# SENSORS.net
KiCad netlist of a schematic drawn in Altium Designer
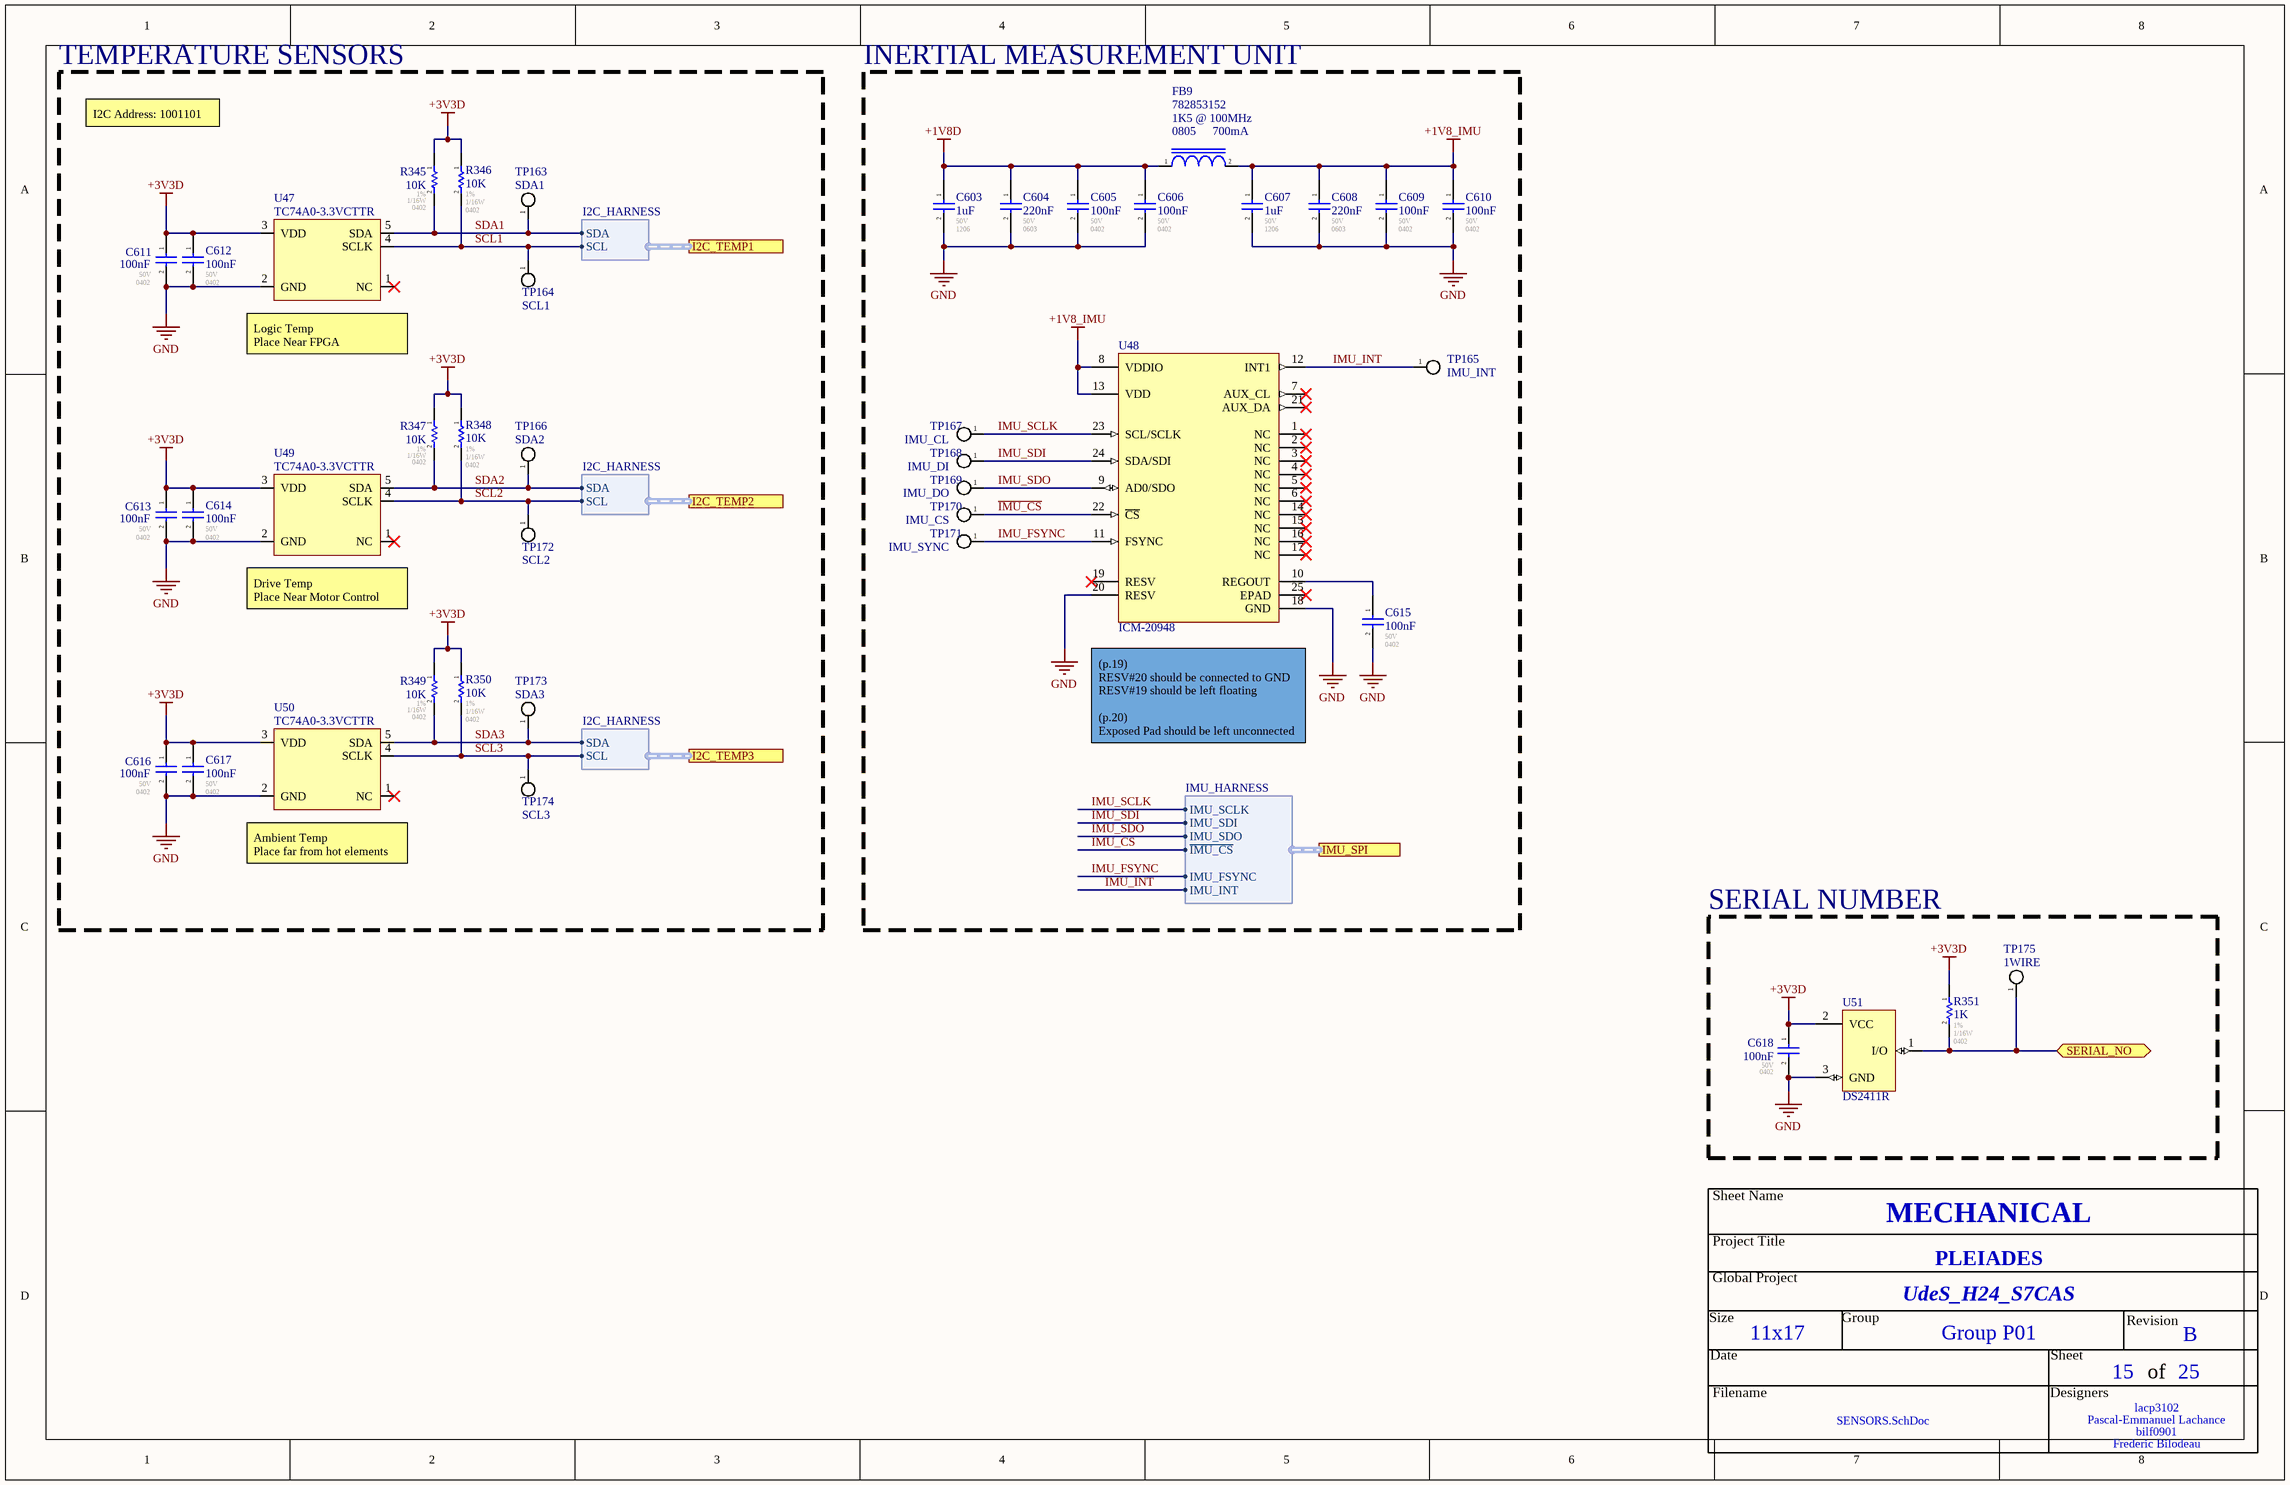
[diagram p0: SENSORS.SchDoc]

(export (version "E")
  (design (tool "Eeschema 10.0.6"))
  (components
    (comp (ref "C603")
      (value "1uF")
      (footprint "1206")
      (description "GCJ31CR71H105KA12L\r\n1206 1uF 10% X7R Ceramic Capacitor")
      (fields
        (field (name "MFR") "Murata")
        (field (name "PART#") "GCJ31CR71H105KA12L")
        (field (name "VOLTAGE - RATED") "50V")
      )
      (libsource (lib "Symbols") (part "CAP_CER"))
    )
    (comp (ref "C604")
      (value "220nF")
      (footprint "0603")
      (description "GCM188R71H224KA64D\r\n0603 220nF 10% X7R Ceramic Capacitor")
      (fields
        (field (name "MFR") "Murata")
        (field (name "PART#") "GCM188R71H224KA64D")
        (field (name "VOLTAGE - RATED") "50V")
      )
      (libsource (lib "Symbols") (part "CAP_CER"))
    )
    (comp (ref "C605")
      (value "100nF")
      (footprint "0402")
      (description "GCM155R71H104KE02J\r\n0402 100nF 10% X7R Ceramic Capacitor")
      (fields
        (field (name "MFR") "Murata")
        (field (name "PART#") "GCM155R71H104KE02J")
        (field (name "VOLTAGE - RATED") "50V")
      )
      (libsource (lib "Symbols") (part "CAP_CER"))
    )
    (comp (ref "C606")
      (value "100nF")
      (footprint "0402")
      (description "GCM155R71H104KE02J\r\n0402 100nF 10% X7R Ceramic Capacitor")
      (fields
        (field (name "MFR") "Murata")
        (field (name "PART#") "GCM155R71H104KE02J")
        (field (name "VOLTAGE - RATED") "50V")
      )
      (libsource (lib "Symbols") (part "CAP_CER"))
    )
    (comp (ref "C607")
      (value "1uF")
      (footprint "1206")
      (description "GCJ31CR71H105KA12L\r\n1206 1uF 10% X7R Ceramic Capacitor")
      (fields
        (field (name "MFR") "Murata")
        (field (name "PART#") "GCJ31CR71H105KA12L")
        (field (name "VOLTAGE - RATED") "50V")
      )
      (libsource (lib "Symbols") (part "CAP_CER"))
    )
    (comp (ref "C608")
      (value "220nF")
      (footprint "0603")
      (description "GCM188R71H224KA64D\r\n0603 220nF 10% X7R Ceramic Capacitor")
      (fields
        (field (name "MFR") "Murata")
        (field (name "PART#") "GCM188R71H224KA64D")
        (field (name "VOLTAGE - RATED") "50V")
      )
      (libsource (lib "Symbols") (part "CAP_CER"))
    )
    (comp (ref "C609")
      (value "100nF")
      (footprint "0402")
      (description "GCM155R71H104KE02J\r\n0402 100nF 10% X7R Ceramic Capacitor")
      (fields
        (field (name "MFR") "Murata")
        (field (name "PART#") "GCM155R71H104KE02J")
        (field (name "VOLTAGE - RATED") "50V")
      )
      (libsource (lib "Symbols") (part "CAP_CER"))
    )
    (comp (ref "C610")
      (value "100nF")
      (footprint "0402")
      (description "GCM155R71H104KE02J\r\n0402 100nF 10% X7R Ceramic Capacitor")
      (fields
        (field (name "MFR") "Murata")
        (field (name "PART#") "GCM155R71H104KE02J")
        (field (name "VOLTAGE - RATED") "50V")
      )
      (libsource (lib "Symbols") (part "CAP_CER"))
    )
    (comp (ref "C611")
      (value "100nF")
      (footprint "0402")
      (description "GCM155R71H104KE02J\r\n0402 100nF 10% X7R Ceramic Capacitor")
      (fields
        (field (name "MFR") "Murata")
        (field (name "PART#") "GCM155R71H104KE02J")
        (field (name "VOLTAGE - RATED") "50V")
      )
      (libsource (lib "Symbols") (part "CAP_CER"))
    )
    (comp (ref "C612")
      (value "100nF")
      (footprint "0402")
      (description "GCM155R71H104KE02J\r\n0402 100nF 10% X7R Ceramic Capacitor")
      (fields
        (field (name "MFR") "Murata")
        (field (name "PART#") "GCM155R71H104KE02J")
        (field (name "VOLTAGE - RATED") "50V")
      )
      (libsource (lib "Symbols") (part "CAP_CER"))
    )
    (comp (ref "C613")
      (value "100nF")
      (footprint "0402")
      (description "GCM155R71H104KE02J\r\n0402 100nF 10% X7R Ceramic Capacitor")
      (fields
        (field (name "MFR") "Murata")
        (field (name "PART#") "GCM155R71H104KE02J")
        (field (name "VOLTAGE - RATED") "50V")
      )
      (libsource (lib "Symbols") (part "CAP_CER"))
    )
    (comp (ref "C614")
      (value "100nF")
      (footprint "0402")
      (description "GCM155R71H104KE02J\r\n0402 100nF 10% X7R Ceramic Capacitor")
      (fields
        (field (name "MFR") "Murata")
        (field (name "PART#") "GCM155R71H104KE02J")
        (field (name "VOLTAGE - RATED") "50V")
      )
      (libsource (lib "Symbols") (part "CAP_CER"))
    )
    (comp (ref "C615")
      (value "100nF")
      (footprint "0402")
      (description "GCM155R71H104KE02J\r\n0402 100nF 10% X7R Ceramic Capacitor")
      (fields
        (field (name "MFR") "Murata")
        (field (name "PART#") "GCM155R71H104KE02J")
        (field (name "VOLTAGE - RATED") "50V")
      )
      (libsource (lib "Symbols") (part "CAP_CER"))
    )
    (comp (ref "C616")
      (value "100nF")
      (footprint "0402")
      (description "GCM155R71H104KE02J\r\n0402 100nF 10% X7R Ceramic Capacitor")
      (fields
        (field (name "MFR") "Murata")
        (field (name "PART#") "GCM155R71H104KE02J")
        (field (name "VOLTAGE - RATED") "50V")
      )
      (libsource (lib "Symbols") (part "CAP_CER"))
    )
    (comp (ref "C617")
      (value "100nF")
      (footprint "0402")
      (description "GCM155R71H104KE02J\r\n0402 100nF 10% X7R Ceramic Capacitor")
      (fields
        (field (name "MFR") "Murata")
        (field (name "PART#") "GCM155R71H104KE02J")
        (field (name "VOLTAGE - RATED") "50V")
      )
      (libsource (lib "Symbols") (part "CAP_CER"))
    )
    (comp (ref "C618")
      (value "100nF")
      (footprint "0402")
      (description "GCM155R71H104KE02J\r\n0402 100nF 10% X7R Ceramic Capacitor")
      (fields
        (field (name "MFR") "Murata")
        (field (name "PART#") "GCM155R71H104KE02J")
        (field (name "VOLTAGE - RATED") "50V")
      )
      (libsource (lib "Symbols") (part "CAP_CER"))
    )
    (comp (ref "FB9")
      (value "782853152")
      (footprint "IND_0805")
      (description "600 Ohms @ 100 MHz 1 Signal Line Ferrite Bead 0603 (1608 Metric) 1A 200mOhm")
      (fields
        (field (name "IMPEDANCE @ FREQ") "1K5 @ 100MHz")
        (field (name "PACKAGE / CASE") "0805")
        (field (name "CURRENT RATING") "700mA")
        (field (name "MANUFACTURER") "Wurth Elektronik")
      )
      (libsource (lib "Symbols") (part "FERRITE_BEAD"))
    )
    (comp (ref "R345")
      (value "10K")
      (footprint "RES_0402")
      (fields
        (field (name "TOLERANCE") "1%")
        (field (name "POWER") "1/16W")
        (field (name "PACKAGE / CASE") "0402")
      )
      (libsource (lib "Symbols") (part "RESISTOR"))
    )
    (comp (ref "R346")
      (value "10K")
      (footprint "RES_0402")
      (fields
        (field (name "TOLERANCE") "1%")
        (field (name "POWER") "1/16W")
        (field (name "PACKAGE / CASE") "0402")
      )
      (libsource (lib "Symbols") (part "RESISTOR"))
    )
    (comp (ref "R347")
      (value "10K")
      (footprint "RES_0402")
      (fields
        (field (name "TOLERANCE") "1%")
        (field (name "POWER") "1/16W")
        (field (name "PACKAGE / CASE") "0402")
      )
      (libsource (lib "Symbols") (part "RESISTOR"))
    )
    (comp (ref "R348")
      (value "10K")
      (footprint "RES_0402")
      (fields
        (field (name "TOLERANCE") "1%")
        (field (name "POWER") "1/16W")
        (field (name "PACKAGE / CASE") "0402")
      )
      (libsource (lib "Symbols") (part "RESISTOR"))
    )
    (comp (ref "R349")
      (value "10K")
      (footprint "RES_0402")
      (fields
        (field (name "TOLERANCE") "1%")
        (field (name "POWER") "1/16W")
        (field (name "PACKAGE / CASE") "0402")
      )
      (libsource (lib "Symbols") (part "RESISTOR"))
    )
    (comp (ref "R350")
      (value "10K")
      (footprint "RES_0402")
      (fields
        (field (name "TOLERANCE") "1%")
        (field (name "POWER") "1/16W")
        (field (name "PACKAGE / CASE") "0402")
      )
      (libsource (lib "Symbols") (part "RESISTOR"))
    )
    (comp (ref "R351")
      (value "1K")
      (footprint "RES_0402")
      (fields
        (field (name "TOLERANCE") "1%")
        (field (name "POWER") "1/16W")
        (field (name "PACKAGE / CASE") "0402")
      )
      (libsource (lib "Symbols") (part "RESISTOR"))
    )
    (comp (ref "TP163")
      (value "SDA1")
      (footprint "TP_PAD_SMALL")
      (description "Test Point")
      (libsource (lib "Symbols") (part "TESTPOINT_PAD_SMALL"))
    )
    (comp (ref "TP164")
      (value "SCL1")
      (footprint "TP_PAD_SMALL")
      (description "Test Point")
      (libsource (lib "Symbols") (part "TESTPOINT_PAD_SMALL"))
    )
    (comp (ref "TP165")
      (value "IMU_INT")
      (footprint "TP_PAD_SMALL")
      (description "Test Point")
      (libsource (lib "Symbols") (part "TESTPOINT_PAD_SMALL"))
    )
    (comp (ref "TP166")
      (value "SDA2")
      (footprint "TP_PAD_SMALL")
      (description "Test Point")
      (libsource (lib "Symbols") (part "TESTPOINT_PAD_SMALL"))
    )
    (comp (ref "TP167")
      (value "IMU_CL")
      (footprint "TP_PAD_SMALL")
      (description "Test Point")
      (libsource (lib "Symbols") (part "TESTPOINT_PAD_SMALL"))
    )
    (comp (ref "TP168")
      (value "IMU_DI")
      (footprint "TP_PAD_SMALL")
      (description "Test Point")
      (libsource (lib "Symbols") (part "TESTPOINT_PAD_SMALL"))
    )
    (comp (ref "TP169")
      (value "IMU_DO")
      (footprint "TP_PAD_SMALL")
      (description "Test Point")
      (libsource (lib "Symbols") (part "TESTPOINT_PAD_SMALL"))
    )
    (comp (ref "TP170")
      (value "IMU_CS")
      (footprint "TP_PAD_SMALL")
      (description "Test Point")
      (libsource (lib "Symbols") (part "TESTPOINT_PAD_SMALL"))
    )
    (comp (ref "TP171")
      (value "IMU_SYNC")
      (footprint "TP_PAD_SMALL")
      (description "Test Point")
      (libsource (lib "Symbols") (part "TESTPOINT_PAD_SMALL"))
    )
    (comp (ref "TP172")
      (value "SCL2")
      (footprint "TP_PAD_SMALL")
      (description "Test Point")
      (libsource (lib "Symbols") (part "TESTPOINT_PAD_SMALL"))
    )
    (comp (ref "TP173")
      (value "SDA3")
      (footprint "TP_PAD_SMALL")
      (description "Test Point")
      (libsource (lib "Symbols") (part "TESTPOINT_PAD_SMALL"))
    )
    (comp (ref "TP174")
      (value "SCL3")
      (footprint "TP_PAD_SMALL")
      (description "Test Point")
      (libsource (lib "Symbols") (part "TESTPOINT_PAD_SMALL"))
    )
    (comp (ref "TP175")
      (value "1WIRE")
      (footprint "TP_PAD_SMALL")
      (description "Test Point")
      (libsource (lib "Symbols") (part "TESTPOINT_PAD_SMALL"))
    )
    (comp (ref "U47")
      (value "TC74A0-3.3VCTTR")
      (footprint "SEN_TEMP_TC74A0-3.3VCTTR")
      (description "SENS - TEMPERATURE SENSOR I2C/SMBUS - SOT23-5")
      (fields
        (field (name "VOLTAGE") "2.7 V ~ 5.5 V")
        (field (name "MFG") "Microchip")
        (field (name "CREATEDBY") "Jonathan Bouchard")
      )
      (libsource (lib "S7CAS_LIB2023") (part "SENS_TEMP_TC74A0-3.3VCTTR"))
    )
    (comp (ref "U48")
      (value "ICM-20948")
      (footprint "QFN-24_3X3")
      (description "Accelerometer, Gyroscope, Magnetometer, 9 Axis Sensor I2C, SPI Output")
      (fields (field (name "MFR") "TDK InvenSense"))
      (libsource (lib "Misc") (part "ICM-20948"))
    )
    (comp (ref "U49")
      (value "TC74A0-3.3VCTTR")
      (footprint "SEN_TEMP_TC74A0-3.3VCTTR")
      (description "SENS - TEMPERATURE SENSOR I2C/SMBUS - SOT23-5")
      (fields
        (field (name "VOLTAGE") "2.7 V ~ 5.5 V")
        (field (name "MFG") "Microchip")
        (field (name "CREATEDBY") "Jonathan Bouchard")
      )
      (libsource (lib "S7CAS_LIB2023") (part "SENS_TEMP_TC74A0-3.3VCTTR"))
    )
    (comp (ref "U50")
      (value "TC74A0-3.3VCTTR")
      (footprint "SEN_TEMP_TC74A0-3.3VCTTR")
      (description "SENS - TEMPERATURE SENSOR I2C/SMBUS - SOT23-5")
      (fields
        (field (name "VOLTAGE") "2.7 V ~ 5.5 V")
        (field (name "MFG") "Microchip")
        (field (name "CREATEDBY") "Jonathan Bouchard")
      )
      (libsource (lib "S7CAS_LIB2023") (part "SENS_TEMP_TC74A0-3.3VCTTR"))
    )
    (comp (ref "U51")
      (value "DS2411R")
      (footprint "SOT23-3")
      (description "Silicon Serial Number SOT-23-3")
      (fields (field (name "MFR") "Analog Devices"))
      (libsource (lib "Misc") (part "DS2411R"))
    )
  )
  (nets
    (net (code "3") (name "+1V8D") (class "Default")
      (node (ref "C603") (pin "1") (pinfunction "1_1") (pintype "passive"))
      (node (ref "C604") (pin "1") (pinfunction "1_1") (pintype "passive"))
      (node (ref "C605") (pin "1") (pinfunction "1_1") (pintype "passive"))
      (node (ref "C606") (pin "1") (pinfunction "1_1") (pintype "passive"))
      (node (ref "FB9") (pin "1") (pinfunction "1_1") (pintype "passive"))
    )
    (net (code "4") (name "+1V8_IMU") (class "Default")
      (node (ref "C607") (pin "1") (pinfunction "1_1") (pintype "passive"))
      (node (ref "C608") (pin "1") (pinfunction "1_1") (pintype "passive"))
      (node (ref "C609") (pin "1") (pinfunction "1_1") (pintype "passive"))
      (node (ref "C610") (pin "1") (pinfunction "1_1") (pintype "passive"))
      (node (ref "FB9") (pin "2") (pinfunction "2_2") (pintype "passive"))
      (node (ref "U48") (pin "13") (pinfunction "VDD_13") (pintype "power_in"))
      (node (ref "U48") (pin "8") (pinfunction "VDDIO_8") (pintype "power_in"))
    )
    (net (code "5") (name "+3V3D") (class "Default")
      (node (ref "C611") (pin "1") (pinfunction "1_1") (pintype "passive"))
      (node (ref "C612") (pin "1") (pinfunction "1_1") (pintype "passive"))
      (node (ref "C613") (pin "1") (pinfunction "1_1") (pintype "passive"))
      (node (ref "C614") (pin "1") (pinfunction "1_1") (pintype "passive"))
      (node (ref "C616") (pin "1") (pinfunction "1_1") (pintype "passive"))
      (node (ref "C617") (pin "1") (pinfunction "1_1") (pintype "passive"))
      (node (ref "C618") (pin "1") (pinfunction "1_1") (pintype "passive"))
      (node (ref "R345") (pin "1") (pinfunction "1_1") (pintype "passive"))
      (node (ref "R346") (pin "1") (pinfunction "1_1") (pintype "passive"))
      (node (ref "R347") (pin "1") (pinfunction "1_1") (pintype "passive"))
      (node (ref "R348") (pin "1") (pinfunction "1_1") (pintype "passive"))
      (node (ref "R349") (pin "1") (pinfunction "1_1") (pintype "passive"))
      (node (ref "R350") (pin "1") (pinfunction "1_1") (pintype "passive"))
      (node (ref "R351") (pin "1") (pinfunction "1_1") (pintype "passive"))
      (node (ref "U47") (pin "3") (pinfunction "VDD_3") (pintype "passive"))
      (node (ref "U49") (pin "3") (pinfunction "VDD_3") (pintype "passive"))
      (node (ref "U50") (pin "3") (pinfunction "VDD_3") (pintype "passive"))
      (node (ref "U51") (pin "2") (pinfunction "VCC_2") (pintype "power_in"))
    )
    (net (code "6") (name "/IMU_CS") (class "Default")
      (node (ref "TP170") (pin "1") (pinfunction "A_1") (pintype "passive"))
      (node (ref "U48") (pin "22") (pinfunction "CS_22") (pintype "input"))
    )
    (net (code "7") (name "/IMU_FSYNC") (class "Default")
      (node (ref "TP171") (pin "1") (pinfunction "A_1") (pintype "passive"))
      (node (ref "U48") (pin "11") (pinfunction "FSYNC_11") (pintype "input"))
    )
    (net (code "8") (name "/IMU_INT") (class "Default")
      (node (ref "TP165") (pin "1") (pinfunction "A_1") (pintype "passive"))
      (node (ref "U48") (pin "12") (pinfunction "INT1_12") (pintype "output"))
    )
    (net (code "9") (name "/IMU_SCLK") (class "Default")
      (node (ref "TP167") (pin "1") (pinfunction "A_1") (pintype "passive"))
      (node (ref "U48") (pin "23") (pinfunction "SCL/SCLK_23") (pintype "input"))
    )
    (net (code "10") (name "/IMU_SDI") (class "Default")
      (node (ref "TP168") (pin "1") (pinfunction "A_1") (pintype "passive"))
      (node (ref "U48") (pin "24") (pinfunction "SDA/SDI_24") (pintype "input"))
    )
    (net (code "11") (name "/IMU_SDO") (class "Default")
      (node (ref "TP169") (pin "1") (pinfunction "A_1") (pintype "passive"))
      (node (ref "U48") (pin "9") (pinfunction "AD0/SDO_9") (pintype "bidirectional"))
    )
    (net (code "12") (name "/SCL1") (class "Default")
      (node (ref "R346") (pin "2") (pinfunction "2_2") (pintype "passive"))
      (node (ref "TP164") (pin "1") (pinfunction "A_1") (pintype "passive"))
      (node (ref "U47") (pin "4") (pinfunction "SCLK_4") (pintype "passive"))
    )
    (net (code "13") (name "/SCL2") (class "Default")
      (node (ref "R348") (pin "2") (pinfunction "2_2") (pintype "passive"))
      (node (ref "TP172") (pin "1") (pinfunction "A_1") (pintype "passive"))
      (node (ref "U49") (pin "4") (pinfunction "SCLK_4") (pintype "passive"))
    )
    (net (code "14") (name "/SCL3") (class "Default")
      (node (ref "R350") (pin "2") (pinfunction "2_2") (pintype "passive"))
      (node (ref "TP174") (pin "1") (pinfunction "A_1") (pintype "passive"))
      (node (ref "U50") (pin "4") (pinfunction "SCLK_4") (pintype "passive"))
    )
    (net (code "15") (name "/SDA1") (class "Default")
      (node (ref "R345") (pin "2") (pinfunction "2_2") (pintype "passive"))
      (node (ref "TP163") (pin "1") (pinfunction "A_1") (pintype "passive"))
      (node (ref "U47") (pin "5") (pinfunction "SDA_5") (pintype "passive"))
    )
    (net (code "16") (name "/SDA2") (class "Default")
      (node (ref "R347") (pin "2") (pinfunction "2_2") (pintype "passive"))
      (node (ref "TP166") (pin "1") (pinfunction "A_1") (pintype "passive"))
      (node (ref "U49") (pin "5") (pinfunction "SDA_5") (pintype "passive"))
    )
    (net (code "17") (name "/SDA3") (class "Default")
      (node (ref "R349") (pin "2") (pinfunction "2_2") (pintype "passive"))
      (node (ref "TP173") (pin "1") (pinfunction "A_1") (pintype "passive"))
      (node (ref "U50") (pin "5") (pinfunction "SDA_5") (pintype "passive"))
    )
    (net (code "18") (name "/SERIAL_NO") (class "Default")
      (node (ref "R351") (pin "2") (pinfunction "2_2") (pintype "passive"))
      (node (ref "TP175") (pin "1") (pinfunction "A_1") (pintype "passive"))
      (node (ref "U51") (pin "1") (pinfunction "I/O_1") (pintype "bidirectional"))
    )
    (net (code "21") (name "GND") (class "Default")
      (node (ref "C603") (pin "2") (pinfunction "2_2") (pintype "passive"))
      (node (ref "C604") (pin "2") (pinfunction "2_2") (pintype "passive"))
      (node (ref "C605") (pin "2") (pinfunction "2_2") (pintype "passive"))
      (node (ref "C606") (pin "2") (pinfunction "2_2") (pintype "passive"))
      (node (ref "C607") (pin "2") (pinfunction "2_2") (pintype "passive"))
      (node (ref "C608") (pin "2") (pinfunction "2_2") (pintype "passive"))
      (node (ref "C609") (pin "2") (pinfunction "2_2") (pintype "passive"))
      (node (ref "C610") (pin "2") (pinfunction "2_2") (pintype "passive"))
      (node (ref "C611") (pin "2") (pinfunction "2_2") (pintype "passive"))
      (node (ref "C612") (pin "2") (pinfunction "2_2") (pintype "passive"))
      (node (ref "C613") (pin "2") (pinfunction "2_2") (pintype "passive"))
      (node (ref "C614") (pin "2") (pinfunction "2_2") (pintype "passive"))
      (node (ref "C615") (pin "2") (pinfunction "2_2") (pintype "passive"))
      (node (ref "C616") (pin "2") (pinfunction "2_2") (pintype "passive"))
      (node (ref "C617") (pin "2") (pinfunction "2_2") (pintype "passive"))
      (node (ref "C618") (pin "2") (pinfunction "2_2") (pintype "passive"))
      (node (ref "U47") (pin "2") (pinfunction "GND_2") (pintype "passive"))
      (node (ref "U48") (pin "18") (pinfunction "GND_18") (pintype "power_in"))
      (node (ref "U48") (pin "20") (pinfunction "RESV_20") (pintype "passive"))
      (node (ref "U49") (pin "2") (pinfunction "GND_2") (pintype "passive"))
      (node (ref "U50") (pin "2") (pinfunction "GND_2") (pintype "passive"))
      (node (ref "U51") (pin "3") (pinfunction "GND_3") (pintype "bidirectional"))
    )
    (net (code "22") (name "Net-(U48-REGOUT)") (class "Default")
      (node (ref "C615") (pin "1") (pinfunction "1_1") (pintype "passive"))
      (node (ref "U48") (pin "10") (pinfunction "REGOUT_10") (pintype "power_in"))
    )
    (net (code "23") (name "unconnected-(U47-NC-Pad1)") (class "Default")
      (node (ref "U47") (pin "1") (pinfunction "NC_1") (pintype "passive+no_connect"))
    )
    (net (code "24") (name "unconnected-(U48-AUX_CL-Pad7)") (class "Default")
      (node (ref "U48") (pin "7") (pinfunction "AUX_CL_7") (pintype "output+no_connect"))
    )
    (net (code "25") (name "unconnected-(U48-AUX_DA-Pad21)") (class "Default")
      (node (ref "U48") (pin "21") (pinfunction "AUX_DA_21") (pintype "output+no_connect"))
    )
    (net (code "26") (name "unconnected-(U48-EPAD-Pad25)") (class "Default")
      (node (ref "U48") (pin "25") (pinfunction "EPAD_25") (pintype "passive+no_connect"))
    )
    (net (code "27") (name "unconnected-(U48-NC-Pad1)") (class "Default")
      (node (ref "U48") (pin "1") (pinfunction "NC_1") (pintype "passive+no_connect"))
    )
    (net (code "28") (name "unconnected-(U48-NC-Pad2)") (class "Default")
      (node (ref "U48") (pin "2") (pinfunction "NC_2") (pintype "passive+no_connect"))
    )
    (net (code "29") (name "unconnected-(U48-NC-Pad3)") (class "Default")
      (node (ref "U48") (pin "3") (pinfunction "NC_3") (pintype "passive+no_connect"))
    )
    (net (code "30") (name "unconnected-(U48-NC-Pad4)") (class "Default")
      (node (ref "U48") (pin "4") (pinfunction "NC_4") (pintype "passive+no_connect"))
    )
    (net (code "31") (name "unconnected-(U48-NC-Pad5)") (class "Default")
      (node (ref "U48") (pin "5") (pinfunction "NC_5") (pintype "passive+no_connect"))
    )
    (net (code "32") (name "unconnected-(U48-NC-Pad6)") (class "Default")
      (node (ref "U48") (pin "6") (pinfunction "NC_6") (pintype "passive+no_connect"))
    )
    (net (code "33") (name "unconnected-(U48-NC-Pad14)") (class "Default")
      (node (ref "U48") (pin "14") (pinfunction "NC_14") (pintype "passive+no_connect"))
    )
    (net (code "34") (name "unconnected-(U48-NC-Pad15)") (class "Default")
      (node (ref "U48") (pin "15") (pinfunction "NC_15") (pintype "passive+no_connect"))
    )
    (net (code "35") (name "unconnected-(U48-NC-Pad16)") (class "Default")
      (node (ref "U48") (pin "16") (pinfunction "NC_16") (pintype "passive+no_connect"))
    )
    (net (code "36") (name "unconnected-(U48-NC-Pad17)") (class "Default")
      (node (ref "U48") (pin "17") (pinfunction "NC_17") (pintype "passive+no_connect"))
    )
    (net (code "37") (name "unconnected-(U48-RESV-Pad19)") (class "Default")
      (node (ref "U48") (pin "19") (pinfunction "RESV_19") (pintype "passive+no_connect"))
    )
    (net (code "38") (name "unconnected-(U49-NC-Pad1)") (class "Default")
      (node (ref "U49") (pin "1") (pinfunction "NC_1") (pintype "passive+no_connect"))
    )
    (net (code "39") (name "unconnected-(U50-NC-Pad1)") (class "Default")
      (node (ref "U50") (pin "1") (pinfunction "NC_1") (pintype "passive+no_connect"))
    )
  )
)
